# NintendoDualLCD.net
KiCad netlist of a schematic drawn in EAGLE
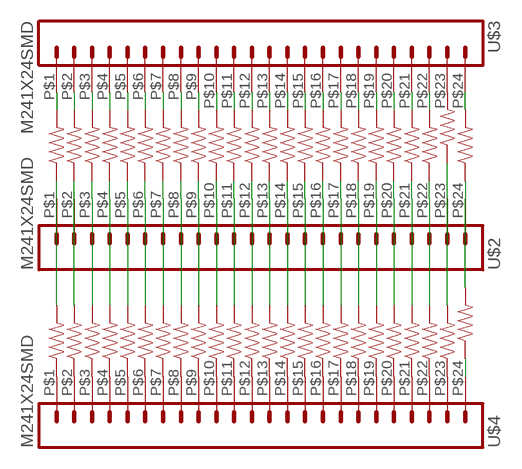
[diagram p0: schematic, sheet 1]

(export (version "E")
  (design (tool "Eeschema 10.0.6"))
  (components
    (comp (ref "R1")
      (value "100")
      (footprint "eagle-import:0603-RES")
      (libsource (lib "eagle-import") (part "RESISTOR0603-RES"))
    )
    (comp (ref "R2")
      (value "100")
      (footprint "eagle-import:0603-RES")
      (libsource (lib "eagle-import") (part "RESISTOR0603-RES"))
    )
    (comp (ref "R3")
      (value "100")
      (footprint "eagle-import:0603-RES")
      (libsource (lib "eagle-import") (part "RESISTOR0603-RES"))
    )
    (comp (ref "R4")
      (value "100")
      (footprint "eagle-import:0603-RES")
      (libsource (lib "eagle-import") (part "RESISTOR0603-RES"))
    )
    (comp (ref "R5")
      (value "100")
      (footprint "eagle-import:0603-RES")
      (libsource (lib "eagle-import") (part "RESISTOR0603-RES"))
    )
    (comp (ref "R6")
      (value "100")
      (footprint "eagle-import:0603-RES")
      (libsource (lib "eagle-import") (part "RESISTOR0603-RES"))
    )
    (comp (ref "R7")
      (value "100")
      (footprint "eagle-import:0603-RES")
      (libsource (lib "eagle-import") (part "RESISTOR0603-RES"))
    )
    (comp (ref "R8")
      (value "100")
      (footprint "eagle-import:0603-RES")
      (libsource (lib "eagle-import") (part "RESISTOR0603-RES"))
    )
    (comp (ref "R9")
      (value "100")
      (footprint "eagle-import:0603-RES")
      (libsource (lib "eagle-import") (part "RESISTOR0603-RES"))
    )
    (comp (ref "R10")
      (value "100")
      (footprint "eagle-import:0603-RES")
      (libsource (lib "eagle-import") (part "RESISTOR0603-RES"))
    )
    (comp (ref "R11")
      (value "100")
      (footprint "eagle-import:0603-RES")
      (libsource (lib "eagle-import") (part "RESISTOR0603-RES"))
    )
    (comp (ref "R12")
      (value "100")
      (footprint "eagle-import:0603-RES")
      (libsource (lib "eagle-import") (part "RESISTOR0603-RES"))
    )
    (comp (ref "R13")
      (value "100")
      (footprint "eagle-import:0603-RES")
      (libsource (lib "eagle-import") (part "RESISTOR0603-RES"))
    )
    (comp (ref "R14")
      (value "100")
      (footprint "eagle-import:0603-RES")
      (libsource (lib "eagle-import") (part "RESISTOR0603-RES"))
    )
    (comp (ref "R15")
      (value "100")
      (footprint "eagle-import:0603-RES")
      (libsource (lib "eagle-import") (part "RESISTOR0603-RES"))
    )
    (comp (ref "R16")
      (value "100")
      (footprint "eagle-import:0603-RES")
      (libsource (lib "eagle-import") (part "RESISTOR0603-RES"))
    )
    (comp (ref "R17")
      (value "100")
      (footprint "eagle-import:0603-RES")
      (libsource (lib "eagle-import") (part "RESISTOR0603-RES"))
    )
    (comp (ref "R18")
      (value "100")
      (footprint "eagle-import:0603-RES")
      (libsource (lib "eagle-import") (part "RESISTOR0603-RES"))
    )
    (comp (ref "R19")
      (value "100")
      (footprint "eagle-import:0603-RES")
      (libsource (lib "eagle-import") (part "RESISTOR0603-RES"))
    )
    (comp (ref "R20")
      (value "100")
      (footprint "eagle-import:0603-RES")
      (libsource (lib "eagle-import") (part "RESISTOR0603-RES"))
    )
    (comp (ref "R21")
      (value "100")
      (footprint "eagle-import:0603-RES")
      (libsource (lib "eagle-import") (part "RESISTOR0603-RES"))
    )
    (comp (ref "R22")
      (value "100")
      (footprint "eagle-import:0603-RES")
      (libsource (lib "eagle-import") (part "RESISTOR0603-RES"))
    )
    (comp (ref "R23")
      (value "100")
      (footprint "eagle-import:0603-RES")
      (libsource (lib "eagle-import") (part "RESISTOR0603-RES"))
    )
    (comp (ref "R24")
      (value "100")
      (footprint "eagle-import:0603-RES")
      (libsource (lib "eagle-import") (part "RESISTOR0603-RES"))
    )
    (comp (ref "R25")
      (value "100")
      (footprint "eagle-import:0603-RES")
      (libsource (lib "eagle-import") (part "RESISTOR0603-RES"))
    )
    (comp (ref "R26")
      (value "100")
      (footprint "eagle-import:0603-RES")
      (libsource (lib "eagle-import") (part "RESISTOR0603-RES"))
    )
    (comp (ref "R27")
      (value "100")
      (footprint "eagle-import:0603-RES")
      (libsource (lib "eagle-import") (part "RESISTOR0603-RES"))
    )
    (comp (ref "R28")
      (value "100")
      (footprint "eagle-import:0603-RES")
      (libsource (lib "eagle-import") (part "RESISTOR0603-RES"))
    )
    (comp (ref "R29")
      (value "100")
      (footprint "eagle-import:0603-RES")
      (libsource (lib "eagle-import") (part "RESISTOR0603-RES"))
    )
    (comp (ref "R30")
      (value "100")
      (footprint "eagle-import:0603-RES")
      (libsource (lib "eagle-import") (part "RESISTOR0603-RES"))
    )
    (comp (ref "R31")
      (value "100")
      (footprint "eagle-import:0603-RES")
      (libsource (lib "eagle-import") (part "RESISTOR0603-RES"))
    )
    (comp (ref "R32")
      (value "100")
      (footprint "eagle-import:0603-RES")
      (libsource (lib "eagle-import") (part "RESISTOR0603-RES"))
    )
    (comp (ref "R33")
      (value "100")
      (footprint "eagle-import:0603-RES")
      (libsource (lib "eagle-import") (part "RESISTOR0603-RES"))
    )
    (comp (ref "R34")
      (value "100")
      (footprint "eagle-import:0603-RES")
      (libsource (lib "eagle-import") (part "RESISTOR0603-RES"))
    )
    (comp (ref "R35")
      (value "100")
      (footprint "eagle-import:0603-RES")
      (libsource (lib "eagle-import") (part "RESISTOR0603-RES"))
    )
    (comp (ref "R36")
      (value "100")
      (footprint "eagle-import:0603-RES")
      (libsource (lib "eagle-import") (part "RESISTOR0603-RES"))
    )
    (comp (ref "R37")
      (value "100")
      (footprint "eagle-import:0603-RES")
      (libsource (lib "eagle-import") (part "RESISTOR0603-RES"))
    )
    (comp (ref "R38")
      (value "100")
      (footprint "eagle-import:0603-RES")
      (libsource (lib "eagle-import") (part "RESISTOR0603-RES"))
    )
    (comp (ref "R39")
      (value "100")
      (footprint "eagle-import:0603-RES")
      (libsource (lib "eagle-import") (part "RESISTOR0603-RES"))
    )
    (comp (ref "R40")
      (value "100")
      (footprint "eagle-import:0603-RES")
      (libsource (lib "eagle-import") (part "RESISTOR0603-RES"))
    )
    (comp (ref "R41")
      (value "100")
      (footprint "eagle-import:0603-RES")
      (libsource (lib "eagle-import") (part "RESISTOR0603-RES"))
    )
    (comp (ref "R42")
      (value "100")
      (footprint "eagle-import:0603-RES")
      (libsource (lib "eagle-import") (part "RESISTOR0603-RES"))
    )
    (comp (ref "R43")
      (value "100")
      (footprint "eagle-import:0603-RES")
      (libsource (lib "eagle-import") (part "RESISTOR0603-RES"))
    )
    (comp (ref "R44")
      (value "100")
      (footprint "eagle-import:0603-RES")
      (libsource (lib "eagle-import") (part "RESISTOR0603-RES"))
    )
    (comp (ref "R45")
      (value "100")
      (footprint "eagle-import:0603-RES")
      (libsource (lib "eagle-import") (part "RESISTOR0603-RES"))
    )
    (comp (ref "R46")
      (value "100")
      (footprint "eagle-import:0603-RES")
      (libsource (lib "eagle-import") (part "RESISTOR0603-RES"))
    )
    (comp (ref "R47")
      (value "100")
      (footprint "eagle-import:0603-RES")
      (libsource (lib "eagle-import") (part "RESISTOR0603-RES"))
    )
    (comp (ref "R48")
      (value "100")
      (footprint "eagle-import:0603-RES")
      (libsource (lib "eagle-import") (part "RESISTOR0603-RES"))
    )
    (comp (ref "U$2")
      (value "M241X24SMD")
      (footprint "eagle-import:1X24SMD")
      (libsource (lib "eagle-import") (part "M241X24SMD"))
    )
    (comp (ref "U$3")
      (value "M241X24SMD")
      (footprint "eagle-import:1X24SMD")
      (libsource (lib "eagle-import") (part "M241X24SMD"))
    )
    (comp (ref "U$4")
      (value "M241X24SMD")
      (footprint "eagle-import:1X24SMD")
      (libsource (lib "eagle-import") (part "M241X24SMD"))
    )
  )
  (nets
    (net (code "1") (name "Net-(U$2-2)") (class "Default")
      (node (ref "R1") (pin "1") (pinfunction "1_1") (pintype "passive"))
      (node (ref "R23") (pin "2") (pinfunction "2_2") (pintype "passive"))
      (node (ref "U$2") (pin "P$1") (pinfunction "2_P$1") (pintype "passive"))
    )
    (net (code "2") (name "Net-(U$2-3)") (class "Default")
      (node (ref "R2") (pin "1") (pinfunction "1_1") (pintype "passive"))
      (node (ref "R24") (pin "2") (pinfunction "2_2") (pintype "passive"))
      (node (ref "U$2") (pin "P$2") (pinfunction "3_P$2") (pintype "passive"))
    )
    (net (code "3") (name "Net-(U$2-4)") (class "Default")
      (node (ref "R25") (pin "2") (pinfunction "2_2") (pintype "passive"))
      (node (ref "R3") (pin "1") (pinfunction "1_1") (pintype "passive"))
      (node (ref "U$2") (pin "P$3") (pinfunction "4_P$3") (pintype "passive"))
    )
    (net (code "4") (name "Net-(U$2-5)") (class "Default")
      (node (ref "R26") (pin "2") (pinfunction "2_2") (pintype "passive"))
      (node (ref "R4") (pin "1") (pinfunction "1_1") (pintype "passive"))
      (node (ref "U$2") (pin "P$4") (pinfunction "5_P$4") (pintype "passive"))
    )
    (net (code "5") (name "Net-(U$2-6)") (class "Default")
      (node (ref "R27") (pin "2") (pinfunction "2_2") (pintype "passive"))
      (node (ref "R5") (pin "1") (pinfunction "1_1") (pintype "passive"))
      (node (ref "U$2") (pin "P$5") (pinfunction "6_P$5") (pintype "passive"))
    )
    (net (code "6") (name "Net-(U$2-7)") (class "Default")
      (node (ref "R28") (pin "2") (pinfunction "2_2") (pintype "passive"))
      (node (ref "R6") (pin "1") (pinfunction "1_1") (pintype "passive"))
      (node (ref "U$2") (pin "P$6") (pinfunction "7_P$6") (pintype "passive"))
    )
    (net (code "7") (name "Net-(U$2-8)") (class "Default")
      (node (ref "R29") (pin "2") (pinfunction "2_2") (pintype "passive"))
      (node (ref "R7") (pin "1") (pinfunction "1_1") (pintype "passive"))
      (node (ref "U$2") (pin "P$7") (pinfunction "8_P$7") (pintype "passive"))
    )
    (net (code "8") (name "Net-(U$2-9)") (class "Default")
      (node (ref "R30") (pin "2") (pinfunction "2_2") (pintype "passive"))
      (node (ref "R8") (pin "1") (pinfunction "1_1") (pintype "passive"))
      (node (ref "U$2") (pin "P$8") (pinfunction "9_P$8") (pintype "passive"))
    )
    (net (code "9") (name "Net-(U$2-10)") (class "Default")
      (node (ref "R31") (pin "2") (pinfunction "2_2") (pintype "passive"))
      (node (ref "R9") (pin "1") (pinfunction "1_1") (pintype "passive"))
      (node (ref "U$2") (pin "P$9") (pinfunction "10_P$9") (pintype "passive"))
    )
    (net (code "10") (name "Net-(U$2-11)") (class "Default")
      (node (ref "R10") (pin "1") (pinfunction "1_1") (pintype "passive"))
      (node (ref "R32") (pin "2") (pinfunction "2_2") (pintype "passive"))
      (node (ref "U$2") (pin "P$10") (pinfunction "11_P$10") (pintype "passive"))
    )
    (net (code "11") (name "Net-(U$2-12)") (class "Default")
      (node (ref "R11") (pin "1") (pinfunction "1_1") (pintype "passive"))
      (node (ref "R34") (pin "2") (pinfunction "2_2") (pintype "passive"))
      (node (ref "U$2") (pin "P$11") (pinfunction "12_P$11") (pintype "passive"))
    )
    (net (code "12") (name "Net-(U$2-13)") (class "Default")
      (node (ref "R12") (pin "1") (pinfunction "1_1") (pintype "passive"))
      (node (ref "R35") (pin "2") (pinfunction "2_2") (pintype "passive"))
      (node (ref "U$2") (pin "P$12") (pinfunction "13_P$12") (pintype "passive"))
    )
    (net (code "13") (name "Net-(U$2-14)") (class "Default")
      (node (ref "R13") (pin "1") (pinfunction "1_1") (pintype "passive"))
      (node (ref "R36") (pin "2") (pinfunction "2_2") (pintype "passive"))
      (node (ref "U$2") (pin "P$13") (pinfunction "14_P$13") (pintype "passive"))
    )
    (net (code "14") (name "Net-(U$2-15)") (class "Default")
      (node (ref "R14") (pin "1") (pinfunction "1_1") (pintype "passive"))
      (node (ref "R37") (pin "2") (pinfunction "2_2") (pintype "passive"))
      (node (ref "U$2") (pin "P$14") (pinfunction "15_P$14") (pintype "passive"))
    )
    (net (code "15") (name "Net-(U$2-16)") (class "Default")
      (node (ref "R15") (pin "1") (pinfunction "1_1") (pintype "passive"))
      (node (ref "R38") (pin "2") (pinfunction "2_2") (pintype "passive"))
      (node (ref "U$2") (pin "P$15") (pinfunction "16_P$15") (pintype "passive"))
    )
    (net (code "16") (name "Net-(U$2-17)") (class "Default")
      (node (ref "R16") (pin "1") (pinfunction "1_1") (pintype "passive"))
      (node (ref "R39") (pin "2") (pinfunction "2_2") (pintype "passive"))
      (node (ref "U$2") (pin "P$16") (pinfunction "17_P$16") (pintype "passive"))
    )
    (net (code "17") (name "Net-(U$2-18)") (class "Default")
      (node (ref "R17") (pin "1") (pinfunction "1_1") (pintype "passive"))
      (node (ref "R40") (pin "2") (pinfunction "2_2") (pintype "passive"))
      (node (ref "U$2") (pin "P$17") (pinfunction "18_P$17") (pintype "passive"))
    )
    (net (code "18") (name "Net-(U$2-19)") (class "Default")
      (node (ref "R18") (pin "1") (pinfunction "1_1") (pintype "passive"))
      (node (ref "R41") (pin "2") (pinfunction "2_2") (pintype "passive"))
      (node (ref "U$2") (pin "P$18") (pinfunction "19_P$18") (pintype "passive"))
    )
    (net (code "19") (name "Net-(U$2-20)") (class "Default")
      (node (ref "R19") (pin "1") (pinfunction "1_1") (pintype "passive"))
      (node (ref "R42") (pin "2") (pinfunction "2_2") (pintype "passive"))
      (node (ref "U$2") (pin "P$19") (pinfunction "20_P$19") (pintype "passive"))
    )
    (net (code "20") (name "Net-(U$2-21)") (class "Default")
      (node (ref "R20") (pin "1") (pinfunction "1_1") (pintype "passive"))
      (node (ref "R43") (pin "2") (pinfunction "2_2") (pintype "passive"))
      (node (ref "U$2") (pin "P$20") (pinfunction "21_P$20") (pintype "passive"))
    )
    (net (code "21") (name "Net-(U$2-22)") (class "Default")
      (node (ref "R21") (pin "1") (pinfunction "1_1") (pintype "passive"))
      (node (ref "R44") (pin "2") (pinfunction "2_2") (pintype "passive"))
      (node (ref "U$2") (pin "P$21") (pinfunction "22_P$21") (pintype "passive"))
    )
    (net (code "22") (name "Net-(U$2-23)") (class "Default")
      (node (ref "R22") (pin "1") (pinfunction "1_1") (pintype "passive"))
      (node (ref "R45") (pin "2") (pinfunction "2_2") (pintype "passive"))
      (node (ref "U$2") (pin "P$22") (pinfunction "23_P$22") (pintype "passive"))
    )
    (net (code "23") (name "Net-(U$2-24)") (class "Default")
      (node (ref "R33") (pin "2") (pinfunction "2_2") (pintype "passive"))
      (node (ref "R46") (pin "1") (pinfunction "1_1") (pintype "passive"))
      (node (ref "U$2") (pin "P$23") (pinfunction "24_P$23") (pintype "passive"))
    )
    (net (code "24") (name "Net-(U$2-25)") (class "Default")
      (node (ref "R47") (pin "1") (pinfunction "1_1") (pintype "passive"))
      (node (ref "R48") (pin "2") (pinfunction "2_2") (pintype "passive"))
      (node (ref "U$2") (pin "P$24") (pinfunction "25_P$24") (pintype "passive"))
    )
    (net (code "25") (name "Net-(U$3-2)") (class "Default")
      (node (ref "R1") (pin "2") (pinfunction "2_2") (pintype "passive"))
      (node (ref "U$3") (pin "P$1") (pinfunction "2_P$1") (pintype "passive"))
    )
    (net (code "26") (name "Net-(U$3-3)") (class "Default")
      (node (ref "R2") (pin "2") (pinfunction "2_2") (pintype "passive"))
      (node (ref "U$3") (pin "P$2") (pinfunction "3_P$2") (pintype "passive"))
    )
    (net (code "27") (name "Net-(U$3-4)") (class "Default")
      (node (ref "R3") (pin "2") (pinfunction "2_2") (pintype "passive"))
      (node (ref "U$3") (pin "P$3") (pinfunction "4_P$3") (pintype "passive"))
    )
    (net (code "28") (name "Net-(U$3-5)") (class "Default")
      (node (ref "R4") (pin "2") (pinfunction "2_2") (pintype "passive"))
      (node (ref "U$3") (pin "P$4") (pinfunction "5_P$4") (pintype "passive"))
    )
    (net (code "29") (name "Net-(U$3-6)") (class "Default")
      (node (ref "R5") (pin "2") (pinfunction "2_2") (pintype "passive"))
      (node (ref "U$3") (pin "P$5") (pinfunction "6_P$5") (pintype "passive"))
    )
    (net (code "30") (name "Net-(U$3-7)") (class "Default")
      (node (ref "R6") (pin "2") (pinfunction "2_2") (pintype "passive"))
      (node (ref "U$3") (pin "P$6") (pinfunction "7_P$6") (pintype "passive"))
    )
    (net (code "31") (name "Net-(U$3-8)") (class "Default")
      (node (ref "R7") (pin "2") (pinfunction "2_2") (pintype "passive"))
      (node (ref "U$3") (pin "P$7") (pinfunction "8_P$7") (pintype "passive"))
    )
    (net (code "32") (name "Net-(U$3-9)") (class "Default")
      (node (ref "R8") (pin "2") (pinfunction "2_2") (pintype "passive"))
      (node (ref "U$3") (pin "P$8") (pinfunction "9_P$8") (pintype "passive"))
    )
    (net (code "33") (name "Net-(U$3-10)") (class "Default")
      (node (ref "R9") (pin "2") (pinfunction "2_2") (pintype "passive"))
      (node (ref "U$3") (pin "P$9") (pinfunction "10_P$9") (pintype "passive"))
    )
    (net (code "34") (name "Net-(U$3-11)") (class "Default")
      (node (ref "R10") (pin "2") (pinfunction "2_2") (pintype "passive"))
      (node (ref "U$3") (pin "P$10") (pinfunction "11_P$10") (pintype "passive"))
    )
    (net (code "35") (name "Net-(U$3-12)") (class "Default")
      (node (ref "R11") (pin "2") (pinfunction "2_2") (pintype "passive"))
      (node (ref "U$3") (pin "P$11") (pinfunction "12_P$11") (pintype "passive"))
    )
    (net (code "36") (name "Net-(U$3-13)") (class "Default")
      (node (ref "R12") (pin "2") (pinfunction "2_2") (pintype "passive"))
      (node (ref "U$3") (pin "P$12") (pinfunction "13_P$12") (pintype "passive"))
    )
    (net (code "37") (name "Net-(U$3-14)") (class "Default")
      (node (ref "R13") (pin "2") (pinfunction "2_2") (pintype "passive"))
      (node (ref "U$3") (pin "P$13") (pinfunction "14_P$13") (pintype "passive"))
    )
    (net (code "38") (name "Net-(U$3-15)") (class "Default")
      (node (ref "R14") (pin "2") (pinfunction "2_2") (pintype "passive"))
      (node (ref "U$3") (pin "P$14") (pinfunction "15_P$14") (pintype "passive"))
    )
    (net (code "39") (name "Net-(U$3-16)") (class "Default")
      (node (ref "R15") (pin "2") (pinfunction "2_2") (pintype "passive"))
      (node (ref "U$3") (pin "P$15") (pinfunction "16_P$15") (pintype "passive"))
    )
    (net (code "40") (name "Net-(U$3-17)") (class "Default")
      (node (ref "R16") (pin "2") (pinfunction "2_2") (pintype "passive"))
      (node (ref "U$3") (pin "P$16") (pinfunction "17_P$16") (pintype "passive"))
    )
    (net (code "41") (name "Net-(U$3-18)") (class "Default")
      (node (ref "R17") (pin "2") (pinfunction "2_2") (pintype "passive"))
      (node (ref "U$3") (pin "P$17") (pinfunction "18_P$17") (pintype "passive"))
    )
    (net (code "42") (name "Net-(U$3-19)") (class "Default")
      (node (ref "R18") (pin "2") (pinfunction "2_2") (pintype "passive"))
      (node (ref "U$3") (pin "P$18") (pinfunction "19_P$18") (pintype "passive"))
    )
    (net (code "43") (name "Net-(U$3-20)") (class "Default")
      (node (ref "R19") (pin "2") (pinfunction "2_2") (pintype "passive"))
      (node (ref "U$3") (pin "P$19") (pinfunction "20_P$19") (pintype "passive"))
    )
    (net (code "44") (name "Net-(U$3-21)") (class "Default")
      (node (ref "R20") (pin "2") (pinfunction "2_2") (pintype "passive"))
      (node (ref "U$3") (pin "P$20") (pinfunction "21_P$20") (pintype "passive"))
    )
    (net (code "45") (name "Net-(U$3-22)") (class "Default")
      (node (ref "R21") (pin "2") (pinfunction "2_2") (pintype "passive"))
      (node (ref "U$3") (pin "P$21") (pinfunction "22_P$21") (pintype "passive"))
    )
    (net (code "46") (name "Net-(U$3-23)") (class "Default")
      (node (ref "R22") (pin "2") (pinfunction "2_2") (pintype "passive"))
      (node (ref "U$3") (pin "P$22") (pinfunction "23_P$22") (pintype "passive"))
    )
    (net (code "47") (name "Net-(U$3-24)") (class "Default")
      (node (ref "R46") (pin "2") (pinfunction "2_2") (pintype "passive"))
      (node (ref "U$3") (pin "P$23") (pinfunction "24_P$23") (pintype "passive"))
    )
    (net (code "48") (name "Net-(U$3-25)") (class "Default")
      (node (ref "R47") (pin "2") (pinfunction "2_2") (pintype "passive"))
      (node (ref "U$3") (pin "P$24") (pinfunction "25_P$24") (pintype "passive"))
    )
    (net (code "49") (name "Net-(U$4-2)") (class "Default")
      (node (ref "R23") (pin "1") (pinfunction "1_1") (pintype "passive"))
      (node (ref "U$4") (pin "P$1") (pinfunction "2_P$1") (pintype "passive"))
    )
    (net (code "50") (name "Net-(U$4-3)") (class "Default")
      (node (ref "R24") (pin "1") (pinfunction "1_1") (pintype "passive"))
      (node (ref "U$4") (pin "P$2") (pinfunction "3_P$2") (pintype "passive"))
    )
    (net (code "51") (name "Net-(U$4-4)") (class "Default")
      (node (ref "R25") (pin "1") (pinfunction "1_1") (pintype "passive"))
      (node (ref "U$4") (pin "P$3") (pinfunction "4_P$3") (pintype "passive"))
    )
    (net (code "52") (name "Net-(U$4-5)") (class "Default")
      (node (ref "R26") (pin "1") (pinfunction "1_1") (pintype "passive"))
      (node (ref "U$4") (pin "P$4") (pinfunction "5_P$4") (pintype "passive"))
    )
    (net (code "53") (name "Net-(U$4-6)") (class "Default")
      (node (ref "R27") (pin "1") (pinfunction "1_1") (pintype "passive"))
      (node (ref "U$4") (pin "P$5") (pinfunction "6_P$5") (pintype "passive"))
    )
    (net (code "54") (name "Net-(U$4-7)") (class "Default")
      (node (ref "R28") (pin "1") (pinfunction "1_1") (pintype "passive"))
      (node (ref "U$4") (pin "P$6") (pinfunction "7_P$6") (pintype "passive"))
    )
    (net (code "55") (name "Net-(U$4-8)") (class "Default")
      (node (ref "R29") (pin "1") (pinfunction "1_1") (pintype "passive"))
      (node (ref "U$4") (pin "P$7") (pinfunction "8_P$7") (pintype "passive"))
    )
    (net (code "56") (name "Net-(U$4-9)") (class "Default")
      (node (ref "R30") (pin "1") (pinfunction "1_1") (pintype "passive"))
      (node (ref "U$4") (pin "P$8") (pinfunction "9_P$8") (pintype "passive"))
    )
    (net (code "57") (name "Net-(U$4-10)") (class "Default")
      (node (ref "R31") (pin "1") (pinfunction "1_1") (pintype "passive"))
      (node (ref "U$4") (pin "P$9") (pinfunction "10_P$9") (pintype "passive"))
    )
    (net (code "58") (name "Net-(U$4-11)") (class "Default")
      (node (ref "R32") (pin "1") (pinfunction "1_1") (pintype "passive"))
      (node (ref "U$4") (pin "P$10") (pinfunction "11_P$10") (pintype "passive"))
    )
    (net (code "59") (name "Net-(U$4-12)") (class "Default")
      (node (ref "R34") (pin "1") (pinfunction "1_1") (pintype "passive"))
      (node (ref "U$4") (pin "P$11") (pinfunction "12_P$11") (pintype "passive"))
    )
    (net (code "60") (name "Net-(U$4-13)") (class "Default")
      (node (ref "R35") (pin "1") (pinfunction "1_1") (pintype "passive"))
      (node (ref "U$4") (pin "P$12") (pinfunction "13_P$12") (pintype "passive"))
    )
    (net (code "61") (name "Net-(U$4-14)") (class "Default")
      (node (ref "R36") (pin "1") (pinfunction "1_1") (pintype "passive"))
      (node (ref "U$4") (pin "P$13") (pinfunction "14_P$13") (pintype "passive"))
    )
    (net (code "62") (name "Net-(U$4-15)") (class "Default")
      (node (ref "R37") (pin "1") (pinfunction "1_1") (pintype "passive"))
      (node (ref "U$4") (pin "P$14") (pinfunction "15_P$14") (pintype "passive"))
    )
    (net (code "63") (name "Net-(U$4-16)") (class "Default")
      (node (ref "R38") (pin "1") (pinfunction "1_1") (pintype "passive"))
      (node (ref "U$4") (pin "P$15") (pinfunction "16_P$15") (pintype "passive"))
    )
    (net (code "64") (name "Net-(U$4-17)") (class "Default")
      (node (ref "R39") (pin "1") (pinfunction "1_1") (pintype "passive"))
      (node (ref "U$4") (pin "P$16") (pinfunction "17_P$16") (pintype "passive"))
    )
    (net (code "65") (name "Net-(U$4-18)") (class "Default")
      (node (ref "R40") (pin "1") (pinfunction "1_1") (pintype "passive"))
      (node (ref "U$4") (pin "P$17") (pinfunction "18_P$17") (pintype "passive"))
    )
    (net (code "66") (name "Net-(U$4-19)") (class "Default")
      (node (ref "R41") (pin "1") (pinfunction "1_1") (pintype "passive"))
      (node (ref "U$4") (pin "P$18") (pinfunction "19_P$18") (pintype "passive"))
    )
    (net (code "67") (name "Net-(U$4-20)") (class "Default")
      (node (ref "R42") (pin "1") (pinfunction "1_1") (pintype "passive"))
      (node (ref "U$4") (pin "P$19") (pinfunction "20_P$19") (pintype "passive"))
    )
    (net (code "68") (name "Net-(U$4-21)") (class "Default")
      (node (ref "R43") (pin "1") (pinfunction "1_1") (pintype "passive"))
      (node (ref "U$4") (pin "P$20") (pinfunction "21_P$20") (pintype "passive"))
    )
    (net (code "69") (name "Net-(U$4-22)") (class "Default")
      (node (ref "R44") (pin "1") (pinfunction "1_1") (pintype "passive"))
      (node (ref "U$4") (pin "P$21") (pinfunction "22_P$21") (pintype "passive"))
    )
    (net (code "70") (name "Net-(U$4-23)") (class "Default")
      (node (ref "R45") (pin "1") (pinfunction "1_1") (pintype "passive"))
      (node (ref "U$4") (pin "P$22") (pinfunction "23_P$22") (pintype "passive"))
    )
    (net (code "71") (name "Net-(U$4-24)") (class "Default")
      (node (ref "R33") (pin "1") (pinfunction "1_1") (pintype "passive"))
      (node (ref "U$4") (pin "P$23") (pinfunction "24_P$23") (pintype "passive"))
    )
    (net (code "72") (name "Net-(U$4-25)") (class "Default")
      (node (ref "R48") (pin "1") (pinfunction "1_1") (pintype "passive"))
      (node (ref "U$4") (pin "P$24") (pinfunction "25_P$24") (pintype "passive"))
    )
  )
)
